# Sheet1.net
KiCad netlist of a schematic drawn in Altium Designer
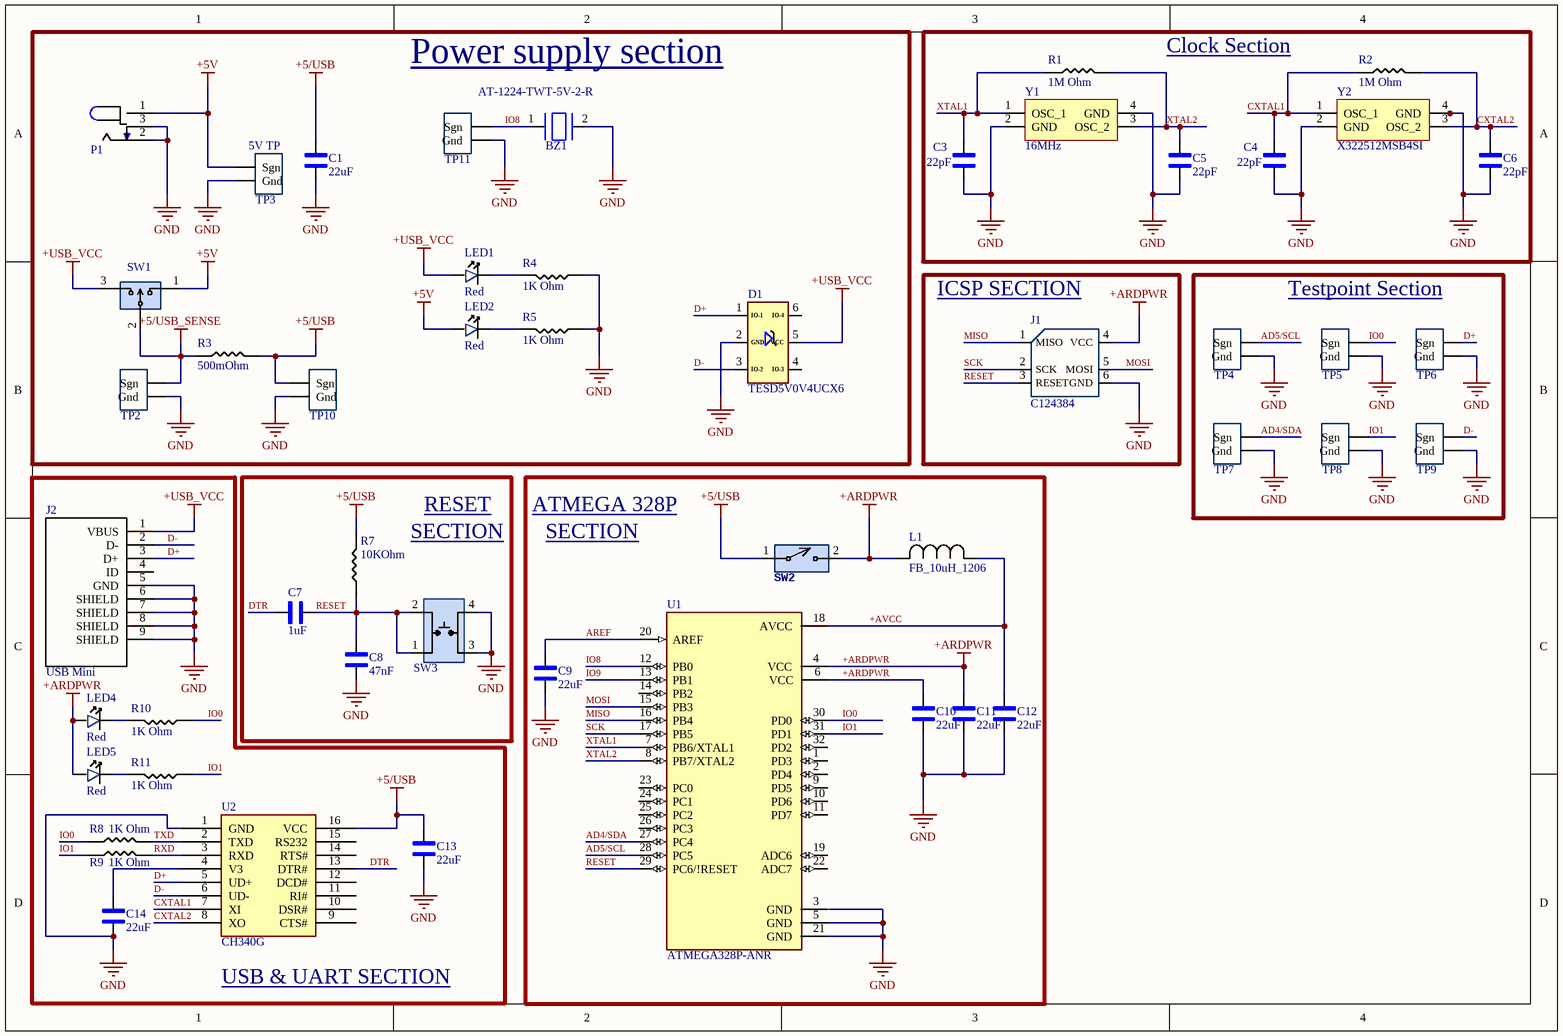
[diagram p0: Sheet1.SchDoc]

(export (version "E")
  (design (tool "Eeschema 10.0.6"))
  (components
    (comp (ref "BZ1")
      (value "AT-1224-TWT-5V-2-R")
      (footprint "BUZZER- TH")
      (fields (field (name "MFR PART #") "AT-1224-TWT-5V-2-R"))
      (libsource (lib "ECEN5730Lib_2023_05_DS (1)") (part "BUZZER_1"))
    )
    (comp (ref "C1")
      (value "22uF")
      (footprint "1206_Passive_Capacitor")
      (description "22uF ±10% 25V X5R 1206 Multilayer Ceramic Capacitors MLCC - SMD/SMT RoHS")
      (fields (field (name "MFR PART #") "CL31A226KAHNNNE") (field (name "LCSC PART#") "C12891"))
      (libsource (lib "ECEN5730Lib_2023_05_DS (1)") (part "C_22uF_1206"))
    )
    (comp (ref "C3")
      (value "22pF")
      (footprint "1206_Passive_Capacitor")
      (description "22pF ±5% 1kV C0G 1206 Multilayer Ceramic Capacitors MLCC - SMD/SMT RoHS")
      (fields (field (name "LCSC PART#") "C107174") (field (name "MFR PART #") "CC1206JKNPOCBN220"))
      (libsource (lib "ECEN5730Lib_2023_05_DS (1)") (part "C_22pF_1206"))
    )
    (comp (ref "C4")
      (value "22pF")
      (footprint "1206_Passive_Capacitor")
      (description "22pF ±5% 1kV C0G 1206 Multilayer Ceramic Capacitors MLCC - SMD/SMT RoHS")
      (fields (field (name "LCSC PART#") "C107174") (field (name "MFR PART #") "CC1206JKNPOCBN220"))
      (libsource (lib "ECEN5730Lib_2023_05_DS (1)") (part "C_22pF_1206"))
    )
    (comp (ref "C5")
      (value "22pF")
      (footprint "1206_Passive_Capacitor")
      (description "22pF ±5% 1kV C0G 1206 Multilayer Ceramic Capacitors MLCC - SMD/SMT RoHS")
      (fields (field (name "LCSC PART#") "C107174") (field (name "MFR PART #") "CC1206JKNPOCBN220"))
      (libsource (lib "ECEN5730Lib_2023_05_DS (1)") (part "C_22pF_1206"))
    )
    (comp (ref "C6")
      (value "22pF")
      (footprint "1206_Passive_Capacitor")
      (description "22pF ±5% 1kV C0G 1206 Multilayer Ceramic Capacitors MLCC - SMD/SMT RoHS")
      (fields (field (name "LCSC PART#") "C107174") (field (name "MFR PART #") "CC1206JKNPOCBN220"))
      (libsource (lib "ECEN5730Lib_2023_05_DS (1)") (part "C_22pF_1206"))
    )
    (comp (ref "C7")
      (value "1uF")
      (footprint "1206_Passive_Capacitor")
      (description "MULTILAYER CERAMIC CAPACITORS MLCC - SMD/SMT 1UF 50V 1206 ROHS")
      (fields (field (name "MFR PART #") "CL31B105KBHNNNE") (field (name "LCSC PART#") "C1848"))
      (libsource (lib "ECEN5730Lib_2023_05_DS (1)") (part "C_1uF_1206"))
    )
    (comp (ref "C8")
      (value "47nF")
      (footprint "1206_Passive_Capacitor")
      (description "47nF ±5% 50V C0G 1206 Multilayer Ceramic Capacitors MLCC - SMD/SMT RoHS")
      (fields (field (name "LCSC PART#") "C21812") (field (name "MFR PART #") "GRM31M5C1H473JA01L"))
      (libsource (lib "ECEN5730Lib_2023_05_DS (1)") (part "C_47nF_1206"))
    )
    (comp (ref "C9")
      (value "22uF")
      (footprint "1206_Passive_Capacitor")
      (description "22uF ±10% 25V X5R 1206 Multilayer Ceramic Capacitors MLCC - SMD/SMT RoHS")
      (fields (field (name "MFR PART #") "CL31A226KAHNNNE") (field (name "LCSC PART#") "C12891"))
      (libsource (lib "ECEN5730Lib_2023_05_DS (1)") (part "C_22uF_1206"))
    )
    (comp (ref "C10")
      (value "22uF")
      (footprint "1206_Passive_Capacitor")
      (description "22uF ±10% 25V X5R 1206 Multilayer Ceramic Capacitors MLCC - SMD/SMT RoHS")
      (fields (field (name "MFR PART #") "CL31A226KAHNNNE") (field (name "LCSC PART#") "C12891"))
      (libsource (lib "ECEN5730Lib_2023_05_DS (1)") (part "C_22uF_1206"))
    )
    (comp (ref "C11")
      (value "22uF")
      (footprint "1206_Passive_Capacitor")
      (description "22uF ±10% 25V X5R 1206 Multilayer Ceramic Capacitors MLCC - SMD/SMT RoHS")
      (fields (field (name "MFR PART #") "CL31A226KAHNNNE") (field (name "LCSC PART#") "C12891"))
      (libsource (lib "ECEN5730Lib_2023_05_DS (1)") (part "C_22uF_1206"))
    )
    (comp (ref "C12")
      (value "22uF")
      (footprint "1206_Passive_Capacitor")
      (description "22uF ±10% 25V X5R 1206 Multilayer Ceramic Capacitors MLCC - SMD/SMT RoHS")
      (fields (field (name "MFR PART #") "CL31A226KAHNNNE") (field (name "LCSC PART#") "C12891"))
      (libsource (lib "ECEN5730Lib_2023_05_DS (1)") (part "C_22uF_1206"))
    )
    (comp (ref "C13")
      (value "22uF")
      (footprint "1206_Passive_Capacitor")
      (description "22uF ±10% 25V X5R 1206 Multilayer Ceramic Capacitors MLCC - SMD/SMT RoHS")
      (fields (field (name "MFR PART #") "CL31A226KAHNNNE") (field (name "LCSC PART#") "C12891"))
      (libsource (lib "ECEN5730Lib_2023_05_DS (1)") (part "C_22uF_1206"))
    )
    (comp (ref "C14")
      (value "22uF")
      (footprint "1206_Passive_Capacitor")
      (description "22uF ±10% 25V X5R 1206 Multilayer Ceramic Capacitors MLCC - SMD/SMT RoHS")
      (fields (field (name "MFR PART #") "CL31A226KAHNNNE") (field (name "LCSC PART#") "C12891"))
      (libsource (lib "ECEN5730Lib_2023_05_DS (1)") (part "C_22uF_1206"))
    )
    (comp (ref "D1")
      (value "TESD5V0V4UCX6")
      (footprint "TVS - TESD")
      (description "TVS SOT-23 ROHS")
      (fields (field (name "LCSC PART#") "C5289077"))
      (libsource (lib "ECEN5730Lib_2023_05_DS_NEW") (part "D_TVS_Diode_TESD"))
    )
    (comp (ref "J1")
      (value "NRPN032PAEN-RC")
      (footprint "ICSP")
      (description "Connector Header Through Hole 6 position 0.079\" (2.00mm)")
      (fields (field (name "LCSC PART#") "C124384"))
      (libsource (lib "ECEN5730Lib_2023_05_DS (1)") (part "J_ICSP"))
    )
    (comp (ref "J2")
      (value "USB Mini")
      (footprint "USB_MINI_B")
      (description "Through Hole USB Connectors RoHS")
      (fields (field (name "LCSC PART#") "C46398") (field (name "MFR PART #") "920-462A2021D10102"))
      (libsource (lib "ECEN5730Lib_2023_05_DS (1)") (part "J_USB_B_Mini"))
    )
    (comp (ref "L1")
      (value "FB_10uH_1206")
      (footprint "AIML-1206_ABR-M")
      (description "25mA 10uH ±10% 800mΩ 1206  Inductors (SMD) ROHS")
      (fields (field (name "MFR PART #") "CMI321609X100KT") (field (name "LCSC PART#") "C1051"))
      (libsource (lib "ECEN5730Lib_2023_05_DS (1)") (part "FB_10uH_1206"))
    )
    (comp (ref "LED1")
      (value "Red")
      (footprint "LED_1206")
      (description "Red 621~631nm 1206 Light Emitting Diodes (LED) RoHS")
      (fields (field (name "MFR PART #") "15-21/R6C-FQ1R1B/2T") (field (name "LCSC PART#") "C93133"))
      (libsource (lib "ECEN5730Lib_2023_05_DS (1)") (part "LED_RED_1206"))
    )
    (comp (ref "LED2")
      (value "Red")
      (footprint "LED_1206")
      (description "Red 621~631nm 1206 Light Emitting Diodes (LED) RoHS")
      (fields (field (name "MFR PART #") "15-21/R6C-FQ1R1B/2T") (field (name "LCSC PART#") "C93133"))
      (libsource (lib "ECEN5730Lib_2023_05_DS (1)") (part "LED_RED_1206"))
    )
    (comp (ref "LED4")
      (value "Red")
      (footprint "LED_1206")
      (description "Red 621~631nm 1206 Light Emitting Diodes (LED) RoHS")
      (fields (field (name "MFR PART #") "15-21/R6C-FQ1R1B/2T") (field (name "LCSC PART#") "C93133"))
      (libsource (lib "ECEN5730Lib_2023_05_DS (1)") (part "LED_RED_1206"))
    )
    (comp (ref "LED5")
      (value "Red")
      (footprint "LED_1206")
      (description "Red 621~631nm 1206 Light Emitting Diodes (LED) RoHS")
      (fields (field (name "MFR PART #") "15-21/R6C-FQ1R1B/2T") (field (name "LCSC PART#") "C93133"))
      (libsource (lib "ECEN5730Lib_2023_05_DS (1)") (part "LED_RED_1206"))
    )
    (comp (ref "P1")
      (value "Power Jack")
      (footprint "Power_Jack")
      (description "Power Barrel Connector Jack 2.10mm ID (0.083\"), 5.50mm OD (0.217\") Through Hole, Right Angle")
      (fields (field (name "MFR PART #") "PJ-102A") (field (name "LCSC PART#") "C136744"))
      (libsource (lib "ECEN5730Lib_2023_05_DS (1)") (part "P_Power Jack"))
    )
    (comp (ref "R1")
      (value "1M Ohm")
      (footprint "1206_Passive_Resitor")
      (description "CHIP RESISTOR - SURFACE MOUNT 1MOHMS ±1% 1/4W 1206 ROHS")
      (fields (field (name "MFR PART #") "RMCF1206JT1M00") (field (name "LCSC PART#") "C17927"))
      (libsource (lib "ECEN5730Lib_2023_05_DS (1)") (part "R_1M_1206"))
    )
    (comp (ref "R2")
      (value "1M Ohm")
      (footprint "1206_Passive_Resitor")
      (description "CHIP RESISTOR - SURFACE MOUNT 1MOHMS ±1% 1/4W 1206 ROHS")
      (fields (field (name "MFR PART #") "RMCF1206JT1M00") (field (name "LCSC PART#") "C17927"))
      (libsource (lib "ECEN5730Lib_2023_05_DS (1)") (part "R_1M_1206"))
    )
    (comp (ref "R3")
      (value "500mOhm")
      (footprint "1206_Passive_Resitor")
      (description "Resistors/Shunt 250mW 500mΩ ±800ppm/℃ ±5% 1206  Current Sense  Resistors ROHS")
      (fields (field (name "MFR PART #") "1206W4J050KT5E") (field (name "LCSC PART#") "C247433"))
      (libsource (lib "ECEN5730Lib_2023_05_DS (1)") (part "R_500mOhm_1206"))
    )
    (comp (ref "R4")
      (value "1K Ohm")
      (footprint "1206_Passive_Resitor")
      (description "CHIP RESISTOR - SURFACE MOUNT 1KOHMS ±1% 1/4W 1206 ROHS")
      (fields (field (name "MFR PART #") "RNCP1206FTD1K00CT") (field (name "LCSC PART#") "C4410"))
      (libsource (lib "ECEN5730Lib_2023_05_DS (1)") (part "R_1K_1206"))
    )
    (comp (ref "R5")
      (value "1K Ohm")
      (footprint "1206_Passive_Resitor")
      (description "CHIP RESISTOR - SURFACE MOUNT 1KOHMS ±1% 1/4W 1206 ROHS")
      (fields (field (name "MFR PART #") "RNCP1206FTD1K00CT") (field (name "LCSC PART#") "C4410"))
      (libsource (lib "ECEN5730Lib_2023_05_DS (1)") (part "R_1K_1206"))
    )
    (comp (ref "R7")
      (value "10KOhm")
      (footprint "1206_Passive_Resitor")
      (description "10 kOhms ±5% 0.25W, 1/4W Chip Resistor 1206 (3216 Metric) Automotive AEC-Q200 Thick Film")
      (fields (field (name "MFR PART #") "RMCF1206FT10K0") (field (name "LCSC PART#") "C17902"))
      (libsource (lib "ECEN5730Lib_2023_05_DS (1)") (part "R_10KOhm_1206"))
    )
    (comp (ref "R8")
      (value "1K Ohm")
      (footprint "1206_Passive_Resitor")
      (description "CHIP RESISTOR - SURFACE MOUNT 1KOHMS ±1% 1/4W 1206 ROHS")
      (fields (field (name "MFR PART #") "RNCP1206FTD1K00CT") (field (name "LCSC PART#") "C4410"))
      (libsource (lib "ECEN5730Lib_2023_05_DS (1)") (part "R_1K_1206"))
    )
    (comp (ref "R9")
      (value "1K Ohm")
      (footprint "1206_Passive_Resitor")
      (description "CHIP RESISTOR - SURFACE MOUNT 1KOHMS ±1% 1/4W 1206 ROHS")
      (fields (field (name "MFR PART #") "RNCP1206FTD1K00CT") (field (name "LCSC PART#") "C4410"))
      (libsource (lib "ECEN5730Lib_2023_05_DS (1)") (part "R_1K_1206"))
    )
    (comp (ref "R10")
      (value "1K Ohm")
      (footprint "1206_Passive_Resitor")
      (description "CHIP RESISTOR - SURFACE MOUNT 1KOHMS ±1% 1/4W 1206 ROHS")
      (fields (field (name "MFR PART #") "RNCP1206FTD1K00CT") (field (name "LCSC PART#") "C4410"))
      (libsource (lib "ECEN5730Lib_2023_05_DS (1)") (part "R_1K_1206"))
    )
    (comp (ref "R11")
      (value "1K Ohm")
      (footprint "1206_Passive_Resitor")
      (description "CHIP RESISTOR - SURFACE MOUNT 1KOHMS ±1% 1/4W 1206 ROHS")
      (fields (field (name "MFR PART #") "RNCP1206FTD1K00CT") (field (name "LCSC PART#") "C4410"))
      (libsource (lib "ECEN5730Lib_2023_05_DS (1)") (part "R_1K_1206"))
    )
    (comp (ref "SW1")
      (value "PREC003SAAN-RC")
      (footprint "3_PIN_100mil")
      (description "Connector Header Through Hole 3 position 0.100\" (2.54mm)")
      (fields (field (name "LCSC PART#") "C49257"))
      (libsource (lib "ECEN5730Lib_2023_05_DS (1)") (part "SW_3Pin_100mil_Switch"))
    )
    (comp (ref "SW2")
      (value "SW_2Pin_100mil_Switch")
      (footprint "2Pin-Header-Conn")
      (description "2Pin Header")
      (fields (field (name "LCSC PART#") "C124375"))
      (libsource (lib "ECEN5730Lib_2023_05_DS (1)") (part "SW_2Pin_100mil_Switch"))
    )
    (comp (ref "SW3")
      (value "TL3305AF160QG")
      (footprint "Switch_JLC")
      (description "Tactile Switch SPST-NO Top Actuated Surface Mount")
      (fields (field (name "MFR PART #") "KH-4.5X4.5X4.3H-STM") (field (name "LCSC PART#") "C2837550"))
      (libsource (lib "ECEN5730Lib_2023_05_DS (1)") (part "SW_Push_Button_JLC"))
    )
    (comp (ref "TP2")
      (value "10x Probe TP")
      (footprint "TP10x_Probe")
      (description "Test Point 300 mil centers")
      (libsource (lib "ECEN5730Lib_2023_05_DS (1)") (part "TP_10x_Probe"))
    )
    (comp (ref "TP3")
      (value "10x Probe TP")
      (footprint "TP10x_Probe")
      (description "Test Point 300 mil centers")
      (libsource (lib "") (part "TP_10x_Probe_1"))
    )
    (comp (ref "TP4")
      (value "10x Probe TP")
      (footprint "TP10x_Probe")
      (description "Test Point 300 mil centers")
      (libsource (lib "ECEN5730Lib_2023_05_DS (1)") (part "TP_10x_Probe"))
    )
    (comp (ref "TP5")
      (value "10x Probe TP")
      (footprint "TP10x_Probe")
      (description "Test Point 300 mil centers")
      (libsource (lib "ECEN5730Lib_2023_05_DS (1)") (part "TP_10x_Probe"))
    )
    (comp (ref "TP6")
      (value "10x Probe TP")
      (footprint "TP10x_Probe")
      (description "Test Point 300 mil centers")
      (libsource (lib "ECEN5730Lib_2023_05_DS (1)") (part "TP_10x_Probe"))
    )
    (comp (ref "TP7")
      (value "10x Probe TP")
      (footprint "TP10x_Probe")
      (description "Test Point 300 mil centers")
      (libsource (lib "ECEN5730Lib_2023_05_DS (1)") (part "TP_10x_Probe"))
    )
    (comp (ref "TP8")
      (value "10x Probe TP")
      (footprint "TP10x_Probe")
      (description "Test Point 300 mil centers")
      (libsource (lib "ECEN5730Lib_2023_05_DS (1)") (part "TP_10x_Probe"))
    )
    (comp (ref "TP9")
      (value "10x Probe TP")
      (footprint "TP10x_Probe")
      (description "Test Point 300 mil centers")
      (libsource (lib "ECEN5730Lib_2023_05_DS (1)") (part "TP_10x_Probe"))
    )
    (comp (ref "TP10")
      (value "10x Probe TP")
      (footprint "TP10x_Probe")
      (description "Test Point 300 mil centers")
      (libsource (lib "") (part "TP_10x_Probe_1"))
    )
    (comp (ref "TP11")
      (value "10x Probe TP")
      (footprint "TP10x_Probe")
      (description "Test Point 300 mil centers")
      (libsource (lib "ECEN5730Lib_2023_05_DS (1)") (part "TP_10x_Probe"))
    )
    (comp (ref "U1")
      (value "ATMEGA328P-ANR")
      (footprint "ATMega328P")
      (description "AVR AVR® ATmega Microcontroller IC 8-Bit 20MHz 32KB (16K x 16) FLASH 32-TQFP (7x7)")
      (fields (field (name "MFR PART #") "ATMEGA328P-AU") (field (name "LCSC PART#") "C14877"))
      (libsource (lib "ECEN5730Lib_2023_05_DS (1)") (part "U_ATMega328P"))
    )
    (comp (ref "U2")
      (value "CH340G")
      (footprint "USB to serial")
      (description "Transceiver USB 2.0 2Mbps SOP-16_150mil USB ICs RoHS")
      (fields (field (name "LCSC PART#") "C14267"))
      (libsource (lib "ECEN5730Lib_2023_05_DS (1)") (part "U_USBtoSerial"))
    )
    (comp (ref "Y1")
      (value "16MHz")
      (footprint "Crystal resonator")
      (description "±10ppm 16000000Hz -40℃~85℃ 贴片无源晶振 60Ω 9pF SMD3225-4P Crystals ROHS")
      (fields (field (name "LCSC PART#") "C13738") (field (name "MFR PART #") "X322516MLB4SI"))
      (libsource (lib "ECEN5730Lib_2023_05_DS (1)") (part "X_16Mhz_Res"))
    )
    (comp (ref "Y2")
      (value "X322512MSB4SI")
      (footprint "Crystal resonator")
      (description "SMD Crystal Resonators 12MHz ±10ppm SMD-3225_4P RoHS")
      (fields (field (name "LCSC PART#") "C9002"))
      (libsource (lib "ECEN5730Lib_2023_05_DS (1)") (part "X_12MHz_Res"))
    )
  )
  (nets
    (net (code "1") (name "+5V") (class "Default")
      (node (ref "LED2") (pin "1") (pinfunction "1_1") (pintype "passive"))
      (node (ref "P1") (pin "1") (pinfunction "1_1") (pintype "power_in"))
      (node (ref "SW1") (pin "1") (pinfunction "1_1") (pintype "passive"))
      (node (ref "TP3") (pin "1") (pinfunction "Sgn_1") (pintype "passive"))
    )
    (net (code "2") (name "+5{slash}USB") (class "Default")
      (node (ref "C1") (pin "2") (pinfunction "2_2") (pintype "passive"))
      (node (ref "C13") (pin "2") (pinfunction "2_2") (pintype "passive"))
      (node (ref "R3") (pin "2") (pinfunction "2_2") (pintype "passive"))
      (node (ref "R7") (pin "2") (pinfunction "2_2") (pintype "passive"))
      (node (ref "SW2") (pin "1") (pinfunction "1_1") (pintype "passive"))
      (node (ref "TP10") (pin "1") (pinfunction "Sgn_1") (pintype "passive"))
      (node (ref "U2") (pin "16") (pinfunction "VCC_16") (pintype "passive"))
    )
    (net (code "3") (name "+5{slash}USB_SENSE") (class "Default")
      (node (ref "R3") (pin "1") (pinfunction "1_1") (pintype "passive"))
      (node (ref "SW1") (pin "2") (pinfunction "2_2") (pintype "passive"))
      (node (ref "TP2") (pin "1") (pinfunction "Sgn_1") (pintype "passive"))
    )
    (net (code "4") (name "+ARDPWR") (class "Default")
      (node (ref "C10") (pin "2") (pinfunction "2_2") (pintype "passive"))
      (node (ref "C11") (pin "2") (pinfunction "2_2") (pintype "passive"))
      (node (ref "J1") (pin "4") (pinfunction "VCC_4") (pintype "passive"))
      (node (ref "L1") (pin "2") (pinfunction "2_2") (pintype "passive"))
      (node (ref "LED4") (pin "1") (pinfunction "1_1") (pintype "passive"))
      (node (ref "LED5") (pin "1") (pinfunction "1_1") (pintype "passive"))
      (node (ref "SW2") (pin "2") (pinfunction "2_2") (pintype "passive"))
      (node (ref "U1") (pin "4") (pinfunction "VCC_4") (pintype "power_in"))
      (node (ref "U1") (pin "6") (pinfunction "VCC_6") (pintype "power_in"))
    )
    (net (code "5") (name "+USB_VCC") (class "Default")
      (node (ref "D1") (pin "5") (pinfunction "VCC_5") (pintype "passive"))
      (node (ref "J2") (pin "1") (pinfunction "VBUS_1") (pintype "passive"))
      (node (ref "LED1") (pin "1") (pinfunction "1_1") (pintype "passive"))
      (node (ref "SW1") (pin "3") (pinfunction "3_3") (pintype "passive"))
    )
    (net (code "6") (name "/+AVCC") (class "Default")
      (node (ref "C12") (pin "2") (pinfunction "2_2") (pintype "passive"))
      (node (ref "L1") (pin "1") (pinfunction "1_1") (pintype "passive"))
      (node (ref "U1") (pin "18") (pinfunction "AVCC_18") (pintype "power_in"))
    )
    (net (code "7") (name "/AD4{slash}SDA") (class "Default")
      (node (ref "TP7") (pin "1") (pinfunction "Sgn_1") (pintype "passive"))
      (node (ref "U1") (pin "27") (pinfunction "PC4_27") (pintype "bidirectional"))
    )
    (net (code "8") (name "/AD5{slash}SCL") (class "Default")
      (node (ref "TP4") (pin "1") (pinfunction "Sgn_1") (pintype "passive"))
      (node (ref "U1") (pin "28") (pinfunction "PC5_28") (pintype "bidirectional"))
    )
    (net (code "9") (name "/AREF") (class "Default")
      (node (ref "C9") (pin "2") (pinfunction "2_2") (pintype "passive"))
      (node (ref "U1") (pin "20") (pinfunction "AREF_20") (pintype "input"))
    )
    (net (code "10") (name "/CXTAL1") (class "Default")
      (node (ref "C4") (pin "2") (pinfunction "2_2") (pintype "passive"))
      (node (ref "R2") (pin "1") (pinfunction "1_1") (pintype "passive"))
      (node (ref "U2") (pin "7") (pinfunction "XI_7") (pintype "passive"))
      (node (ref "Y2") (pin "1") (pinfunction "OSC_1_1") (pintype "passive"))
    )
    (net (code "11") (name "/CXTAL2") (class "Default")
      (node (ref "C6") (pin "2") (pinfunction "2_2") (pintype "passive"))
      (node (ref "R2") (pin "2") (pinfunction "2_2") (pintype "passive"))
      (node (ref "U2") (pin "8") (pinfunction "XO_8") (pintype "passive"))
      (node (ref "Y2") (pin "3") (pinfunction "OSC_2_3") (pintype "passive"))
    )
    (net (code "12") (name "/D+") (class "Default")
      (node (ref "D1") (pin "1") (pinfunction "IO-1_1") (pintype "passive"))
      (node (ref "J2") (pin "3") (pinfunction "D+_3") (pintype "passive"))
      (node (ref "TP6") (pin "1") (pinfunction "Sgn_1") (pintype "passive"))
      (node (ref "U2") (pin "5") (pinfunction "UD+_5") (pintype "passive"))
    )
    (net (code "13") (name "/D-") (class "Default")
      (node (ref "D1") (pin "3") (pinfunction "IO-2_3") (pintype "passive"))
      (node (ref "J2") (pin "2") (pinfunction "D-_2") (pintype "passive"))
      (node (ref "TP9") (pin "1") (pinfunction "Sgn_1") (pintype "passive"))
      (node (ref "U2") (pin "6") (pinfunction "UD-_6") (pintype "passive"))
    )
    (net (code "14") (name "/DTR") (class "Default")
      (node (ref "C7") (pin "2") (pinfunction "2_2") (pintype "passive"))
      (node (ref "U2") (pin "13") (pinfunction "DTR#_13") (pintype "passive"))
    )
    (net (code "15") (name "/IO0") (class "Default")
      (node (ref "R10") (pin "1") (pinfunction "1_1") (pintype "passive"))
      (node (ref "R8") (pin "1") (pinfunction "1_1") (pintype "passive"))
      (node (ref "TP5") (pin "1") (pinfunction "Sgn_1") (pintype "passive"))
      (node (ref "U1") (pin "30") (pinfunction "PD0_30") (pintype "bidirectional"))
    )
    (net (code "16") (name "/IO1") (class "Default")
      (node (ref "R11") (pin "1") (pinfunction "1_1") (pintype "passive"))
      (node (ref "R9") (pin "1") (pinfunction "1_1") (pintype "passive"))
      (node (ref "TP8") (pin "1") (pinfunction "Sgn_1") (pintype "passive"))
      (node (ref "U1") (pin "31") (pinfunction "PD1_31") (pintype "bidirectional"))
    )
    (net (code "17") (name "/IO8") (class "Default")
      (node (ref "BZ1") (pin "1") (pinfunction "BZ1_1") (pintype "passive"))
      (node (ref "TP11") (pin "1") (pinfunction "Sgn_1") (pintype "passive"))
      (node (ref "U1") (pin "12") (pinfunction "PB0_12") (pintype "bidirectional"))
    )
    (net (code "18") (name "/IO9") (class "Default")
      (node (ref "U1") (pin "13") (pinfunction "PB1_13") (pintype "bidirectional"))
    )
    (net (code "19") (name "/MISO") (class "Default")
      (node (ref "J1") (pin "1") (pinfunction "MISO_1") (pintype "passive"))
      (node (ref "U1") (pin "16") (pinfunction "PB4_16") (pintype "bidirectional"))
    )
    (net (code "20") (name "/MOSI") (class "Default")
      (node (ref "J1") (pin "5") (pinfunction "MOSI_5") (pintype "passive"))
      (node (ref "U1") (pin "15") (pinfunction "PB3_15") (pintype "bidirectional"))
    )
    (net (code "21") (name "/RESET") (class "Default")
      (node (ref "C7") (pin "1") (pinfunction "1_1") (pintype "passive"))
      (node (ref "C8") (pin "2") (pinfunction "2_2") (pintype "passive"))
      (node (ref "J1") (pin "3") (pinfunction "RESET_3") (pintype "passive"))
      (node (ref "R7") (pin "1") (pinfunction "1_1") (pintype "passive"))
      (node (ref "SW3") (pin "1") (pinfunction "1_1") (pintype "passive"))
      (node (ref "SW3") (pin "2") (pinfunction "2_2") (pintype "passive"))
      (node (ref "U1") (pin "29") (pinfunction "PC6/!RESET_29") (pintype "bidirectional"))
    )
    (net (code "22") (name "/RXD") (class "Default")
      (node (ref "R9") (pin "2") (pinfunction "2_2") (pintype "passive"))
      (node (ref "U2") (pin "3") (pinfunction "RXD_3") (pintype "passive"))
    )
    (net (code "23") (name "/SCK") (class "Default")
      (node (ref "J1") (pin "2") (pinfunction "SCK_2") (pintype "passive"))
      (node (ref "U1") (pin "17") (pinfunction "PB5_17") (pintype "bidirectional"))
    )
    (net (code "24") (name "/TXD") (class "Default")
      (node (ref "R8") (pin "2") (pinfunction "2_2") (pintype "passive"))
      (node (ref "U2") (pin "2") (pinfunction "TXD_2") (pintype "passive"))
    )
    (net (code "25") (name "/XTAL1") (class "Default")
      (node (ref "C3") (pin "2") (pinfunction "2_2") (pintype "passive"))
      (node (ref "R1") (pin "1") (pinfunction "1_1") (pintype "passive"))
      (node (ref "U1") (pin "7") (pinfunction "PB6/XTAL1_7") (pintype "bidirectional"))
      (node (ref "Y1") (pin "1") (pinfunction "OSC_1_1") (pintype "passive"))
    )
    (net (code "26") (name "/XTAL2") (class "Default")
      (node (ref "C5") (pin "2") (pinfunction "2_2") (pintype "passive"))
      (node (ref "R1") (pin "2") (pinfunction "2_2") (pintype "passive"))
      (node (ref "U1") (pin "8") (pinfunction "PB7/XTAL2_8") (pintype "bidirectional"))
      (node (ref "Y1") (pin "3") (pinfunction "OSC_2_3") (pintype "passive"))
    )
    (net (code "27") (name "GND") (class "Default")
      (node (ref "BZ1") (pin "2") (pinfunction "BZ2_2") (pintype "passive"))
      (node (ref "C1") (pin "1") (pinfunction "1_1") (pintype "passive"))
      (node (ref "C10") (pin "1") (pinfunction "1_1") (pintype "passive"))
      (node (ref "C11") (pin "1") (pinfunction "1_1") (pintype "passive"))
      (node (ref "C12") (pin "1") (pinfunction "1_1") (pintype "passive"))
      (node (ref "C13") (pin "1") (pinfunction "1_1") (pintype "passive"))
      (node (ref "C14") (pin "1") (pinfunction "1_1") (pintype "passive"))
      (node (ref "C3") (pin "1") (pinfunction "1_1") (pintype "passive"))
      (node (ref "C4") (pin "1") (pinfunction "1_1") (pintype "passive"))
      (node (ref "C5") (pin "1") (pinfunction "1_1") (pintype "passive"))
      (node (ref "C6") (pin "1") (pinfunction "1_1") (pintype "passive"))
      (node (ref "C8") (pin "1") (pinfunction "1_1") (pintype "passive"))
      (node (ref "C9") (pin "1") (pinfunction "1_1") (pintype "passive"))
      (node (ref "D1") (pin "2") (pinfunction "GND_2") (pintype "passive"))
      (node (ref "J1") (pin "6") (pinfunction "GND_6") (pintype "passive"))
      (node (ref "J2") (pin "5") (pinfunction "GND_5") (pintype "passive"))
      (node (ref "J2") (pin "6") (pinfunction "SHIELD_6") (pintype "passive"))
      (node (ref "J2") (pin "7") (pinfunction "SHIELD_7") (pintype "passive"))
      (node (ref "J2") (pin "8") (pinfunction "SHIELD_8") (pintype "passive"))
      (node (ref "J2") (pin "9") (pinfunction "SHIELD_9") (pintype "passive"))
      (node (ref "P1") (pin "2") (pinfunction "2_2") (pintype "power_in"))
      (node (ref "P1") (pin "3") (pinfunction "3_3") (pintype "power_in"))
      (node (ref "R4") (pin "1") (pinfunction "1_1") (pintype "passive"))
      (node (ref "R5") (pin "1") (pinfunction "1_1") (pintype "passive"))
      (node (ref "SW3") (pin "3") (pinfunction "3_3") (pintype "passive"))
      (node (ref "SW3") (pin "4") (pinfunction "4_4") (pintype "passive"))
      (node (ref "TP10") (pin "2") (pinfunction "Gnd_2") (pintype "passive"))
      (node (ref "TP11") (pin "2") (pinfunction "Gnd_2") (pintype "passive"))
      (node (ref "TP2") (pin "2") (pinfunction "Gnd_2") (pintype "passive"))
      (node (ref "TP3") (pin "2") (pinfunction "Gnd_2") (pintype "passive"))
      (node (ref "TP4") (pin "2") (pinfunction "Gnd_2") (pintype "passive"))
      (node (ref "TP5") (pin "2") (pinfunction "Gnd_2") (pintype "passive"))
      (node (ref "TP6") (pin "2") (pinfunction "Gnd_2") (pintype "passive"))
      (node (ref "TP7") (pin "2") (pinfunction "Gnd_2") (pintype "passive"))
      (node (ref "TP8") (pin "2") (pinfunction "Gnd_2") (pintype "passive"))
      (node (ref "TP9") (pin "2") (pinfunction "Gnd_2") (pintype "passive"))
      (node (ref "U1") (pin "21") (pinfunction "GND_21") (pintype "power_in"))
      (node (ref "U1") (pin "5") (pinfunction "GND_5") (pintype "power_in"))
      (node (ref "U2") (pin "1") (pinfunction "GND_1") (pintype "passive"))
      (node (ref "Y1") (pin "2") (pinfunction "GND_2") (pintype "passive"))
      (node (ref "Y1") (pin "4") (pinfunction "GND_4") (pintype "passive"))
      (node (ref "Y2") (pin "2") (pinfunction "GND_2") (pintype "passive"))
      (node (ref "Y2") (pin "4") (pinfunction "GND_4") (pintype "passive"))
    )
    (net (code "28") (name "Net-(LED1-Pad2)") (class "Default")
      (node (ref "LED1") (pin "2") (pinfunction "2_2") (pintype "passive"))
      (node (ref "R4") (pin "2") (pinfunction "2_2") (pintype "passive"))
    )
    (net (code "29") (name "Net-(LED2-Pad2)") (class "Default")
      (node (ref "LED2") (pin "2") (pinfunction "2_2") (pintype "passive"))
      (node (ref "R5") (pin "2") (pinfunction "2_2") (pintype "passive"))
    )
    (net (code "30") (name "Net-(LED4-Pad2)") (class "Default")
      (node (ref "LED4") (pin "2") (pinfunction "2_2") (pintype "passive"))
      (node (ref "R10") (pin "2") (pinfunction "2_2") (pintype "passive"))
    )
    (net (code "31") (name "Net-(LED5-Pad2)") (class "Default")
      (node (ref "LED5") (pin "2") (pinfunction "2_2") (pintype "passive"))
      (node (ref "R11") (pin "2") (pinfunction "2_2") (pintype "passive"))
    )
    (net (code "32") (name "Net-(U2-V3)") (class "Default")
      (node (ref "C14") (pin "2") (pinfunction "2_2") (pintype "passive"))
      (node (ref "U2") (pin "4") (pinfunction "V3_4") (pintype "passive"))
    )
    (net (code "33") (name "unconnected-(D1-IO-3-Pad4)") (class "Default")
      (node (ref "D1") (pin "4") (pinfunction "IO-3_4") (pintype "passive"))
    )
    (net (code "34") (name "unconnected-(D1-IO-4-Pad6)") (class "Default")
      (node (ref "D1") (pin "6") (pinfunction "IO-4_6") (pintype "passive"))
    )
    (net (code "35") (name "unconnected-(J2-ID-Pad4)") (class "Default")
      (node (ref "J2") (pin "4") (pinfunction "ID_4") (pintype "passive"))
    )
    (net (code "36") (name "unconnected-(U1-ADC6-Pad19)") (class "Default")
      (node (ref "U1") (pin "19") (pinfunction "ADC6_19") (pintype "bidirectional"))
    )
    (net (code "37") (name "unconnected-(U1-ADC7-Pad22)") (class "Default")
      (node (ref "U1") (pin "22") (pinfunction "ADC7_22") (pintype "bidirectional"))
    )
    (net (code "38") (name "unconnected-(U1-GND-Pad3)") (class "Default")
      (node (ref "U1") (pin "3") (pinfunction "GND_3") (pintype "power_in"))
    )
    (net (code "39") (name "unconnected-(U1-PB2-Pad14)") (class "Default")
      (node (ref "U1") (pin "14") (pinfunction "PB2_14") (pintype "bidirectional"))
    )
    (net (code "40") (name "unconnected-(U1-PC0-Pad23)") (class "Default")
      (node (ref "U1") (pin "23") (pinfunction "PC0_23") (pintype "bidirectional"))
    )
    (net (code "41") (name "unconnected-(U1-PC1-Pad24)") (class "Default")
      (node (ref "U1") (pin "24") (pinfunction "PC1_24") (pintype "bidirectional"))
    )
    (net (code "42") (name "unconnected-(U1-PC2-Pad25)") (class "Default")
      (node (ref "U1") (pin "25") (pinfunction "PC2_25") (pintype "bidirectional"))
    )
    (net (code "43") (name "unconnected-(U1-PC3-Pad26)") (class "Default")
      (node (ref "U1") (pin "26") (pinfunction "PC3_26") (pintype "bidirectional"))
    )
    (net (code "44") (name "unconnected-(U1-PD2-Pad32)") (class "Default")
      (node (ref "U1") (pin "32") (pinfunction "PD2_32") (pintype "bidirectional"))
    )
    (net (code "45") (name "unconnected-(U1-PD3-Pad1)") (class "Default")
      (node (ref "U1") (pin "1") (pinfunction "PD3_1") (pintype "bidirectional"))
    )
    (net (code "46") (name "unconnected-(U1-PD4-Pad2)") (class "Default")
      (node (ref "U1") (pin "2") (pinfunction "PD4_2") (pintype "bidirectional"))
    )
    (net (code "47") (name "unconnected-(U1-PD5-Pad9)") (class "Default")
      (node (ref "U1") (pin "9") (pinfunction "PD5_9") (pintype "bidirectional"))
    )
    (net (code "48") (name "unconnected-(U1-PD6-Pad10)") (class "Default")
      (node (ref "U1") (pin "10") (pinfunction "PD6_10") (pintype "bidirectional"))
    )
    (net (code "49") (name "unconnected-(U1-PD7-Pad11)") (class "Default")
      (node (ref "U1") (pin "11") (pinfunction "PD7_11") (pintype "bidirectional"))
    )
    (net (code "50") (name "unconnected-(U2-CTS#-Pad9)") (class "Default")
      (node (ref "U2") (pin "9") (pinfunction "CTS#_9") (pintype "passive"))
    )
    (net (code "51") (name "unconnected-(U2-DCD#-Pad12)") (class "Default")
      (node (ref "U2") (pin "12") (pinfunction "DCD#_12") (pintype "passive"))
    )
    (net (code "52") (name "unconnected-(U2-DSR#-Pad10)") (class "Default")
      (node (ref "U2") (pin "10") (pinfunction "DSR#_10") (pintype "passive"))
    )
    (net (code "53") (name "unconnected-(U2-RI#-Pad11)") (class "Default")
      (node (ref "U2") (pin "11") (pinfunction "RI#_11") (pintype "passive"))
    )
    (net (code "54") (name "unconnected-(U2-RS232-Pad15)") (class "Default")
      (node (ref "U2") (pin "15") (pinfunction "RS232_15") (pintype "passive"))
    )
    (net (code "55") (name "unconnected-(U2-RTS#-Pad14)") (class "Default")
      (node (ref "U2") (pin "14") (pinfunction "RTS#_14") (pintype "passive"))
    )
  )
)
